# greedy.net
KiCad netlist of a schematic drawn in EAGLE
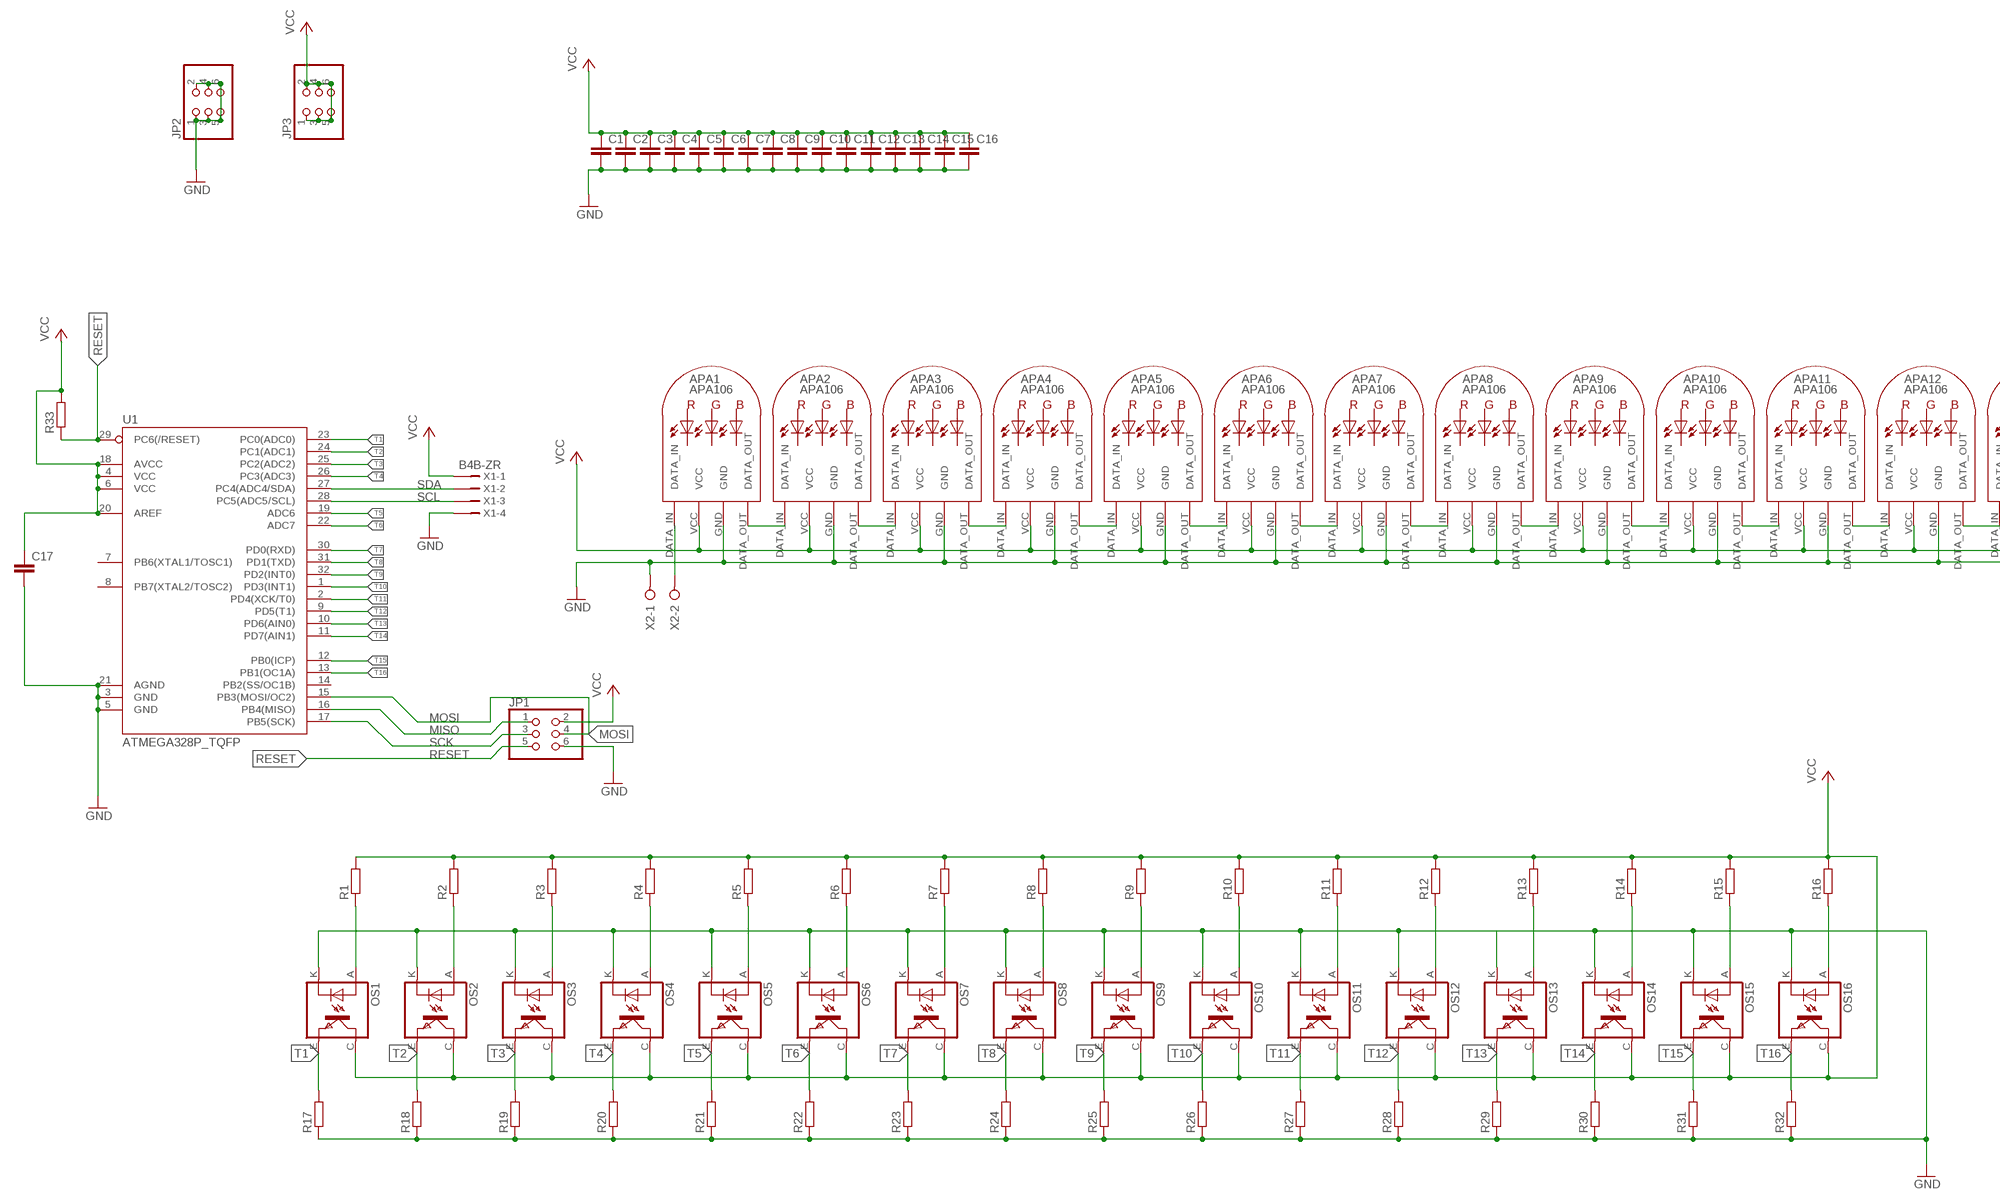
[diagram p0: schematic, sheet 1, part 1 of 2]
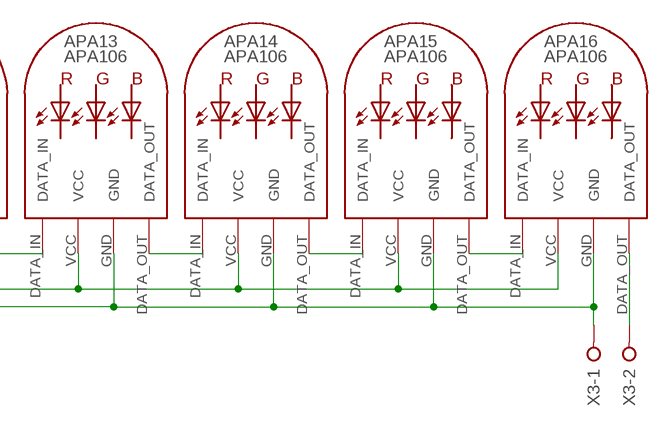
[diagram p1: schematic, sheet 1, part 2 of 2]

(export (version "E")
  (design (tool "Eeschema 10.0.6"))
  (components
    (comp (ref "APA1")
      (value "APA106")
      (footprint "eagle-import:APA_106_8MM")
      (libsource (lib "eagle-import") (part "APA106"))
    )
    (comp (ref "APA2")
      (value "APA106")
      (footprint "eagle-import:APA_106_8MM")
      (libsource (lib "eagle-import") (part "APA106"))
    )
    (comp (ref "APA3")
      (value "APA106")
      (footprint "eagle-import:APA_106_8MM")
      (libsource (lib "eagle-import") (part "APA106"))
    )
    (comp (ref "APA4")
      (value "APA106")
      (footprint "eagle-import:APA_106_8MM")
      (libsource (lib "eagle-import") (part "APA106"))
    )
    (comp (ref "APA5")
      (value "APA106")
      (footprint "eagle-import:APA_106_8MM")
      (libsource (lib "eagle-import") (part "APA106"))
    )
    (comp (ref "APA6")
      (value "APA106")
      (footprint "eagle-import:APA_106_8MM")
      (libsource (lib "eagle-import") (part "APA106"))
    )
    (comp (ref "APA7")
      (value "APA106")
      (footprint "eagle-import:APA_106_8MM")
      (libsource (lib "eagle-import") (part "APA106"))
    )
    (comp (ref "APA8")
      (value "APA106")
      (footprint "eagle-import:APA_106_8MM")
      (libsource (lib "eagle-import") (part "APA106"))
    )
    (comp (ref "APA9")
      (value "APA106")
      (footprint "eagle-import:APA_106_8MM")
      (libsource (lib "eagle-import") (part "APA106"))
    )
    (comp (ref "APA10")
      (value "APA106")
      (footprint "eagle-import:APA_106_8MM")
      (libsource (lib "eagle-import") (part "APA106"))
    )
    (comp (ref "APA11")
      (value "APA106")
      (footprint "eagle-import:APA_106_8MM")
      (libsource (lib "eagle-import") (part "APA106"))
    )
    (comp (ref "APA12")
      (value "APA106")
      (footprint "eagle-import:APA_106_8MM")
      (libsource (lib "eagle-import") (part "APA106"))
    )
    (comp (ref "APA13")
      (value "APA106")
      (footprint "eagle-import:APA_106_8MM")
      (libsource (lib "eagle-import") (part "APA106"))
    )
    (comp (ref "APA14")
      (value "APA106")
      (footprint "eagle-import:APA_106_8MM")
      (libsource (lib "eagle-import") (part "APA106"))
    )
    (comp (ref "APA15")
      (value "APA106")
      (footprint "eagle-import:APA_106_8MM")
      (libsource (lib "eagle-import") (part "APA106"))
    )
    (comp (ref "APA16")
      (value "APA106")
      (footprint "eagle-import:APA_106_8MM")
      (libsource (lib "eagle-import") (part "APA106"))
    )
    (comp (ref "C1")
      (value "C5/3")
      (footprint "eagle-import:C5B3")
      (libsource (lib "eagle-import") (part "C5/3"))
    )
    (comp (ref "C2")
      (value "C5/3")
      (footprint "eagle-import:C5B3")
      (libsource (lib "eagle-import") (part "C5/3"))
    )
    (comp (ref "C3")
      (value "C5/3")
      (footprint "eagle-import:C5B3")
      (libsource (lib "eagle-import") (part "C5/3"))
    )
    (comp (ref "C4")
      (value "C5/3")
      (footprint "eagle-import:C5B3")
      (libsource (lib "eagle-import") (part "C5/3"))
    )
    (comp (ref "C5")
      (value "C5/3")
      (footprint "eagle-import:C5B3")
      (libsource (lib "eagle-import") (part "C5/3"))
    )
    (comp (ref "C6")
      (value "C5/3")
      (footprint "eagle-import:C5B3")
      (libsource (lib "eagle-import") (part "C5/3"))
    )
    (comp (ref "C7")
      (value "C5/3")
      (footprint "eagle-import:C5B3")
      (libsource (lib "eagle-import") (part "C5/3"))
    )
    (comp (ref "C8")
      (value "C5/3")
      (footprint "eagle-import:C5B3")
      (libsource (lib "eagle-import") (part "C5/3"))
    )
    (comp (ref "C9")
      (value "C5/3")
      (footprint "eagle-import:C5B3")
      (libsource (lib "eagle-import") (part "C5/3"))
    )
    (comp (ref "C10")
      (value "C5/3")
      (footprint "eagle-import:C5B3")
      (libsource (lib "eagle-import") (part "C5/3"))
    )
    (comp (ref "C11")
      (value "C5/3")
      (footprint "eagle-import:C5B3")
      (libsource (lib "eagle-import") (part "C5/3"))
    )
    (comp (ref "C12")
      (value "C5/3")
      (footprint "eagle-import:C5B3")
      (libsource (lib "eagle-import") (part "C5/3"))
    )
    (comp (ref "C13")
      (value "C5/3")
      (footprint "eagle-import:C5B3")
      (libsource (lib "eagle-import") (part "C5/3"))
    )
    (comp (ref "C14")
      (value "C5/3")
      (footprint "eagle-import:C5B3")
      (libsource (lib "eagle-import") (part "C5/3"))
    )
    (comp (ref "C15")
      (value "C5/3")
      (footprint "eagle-import:C5B3")
      (libsource (lib "eagle-import") (part "C5/3"))
    )
    (comp (ref "C16")
      (value "C5/3")
      (footprint "eagle-import:C5B3")
      (libsource (lib "eagle-import") (part "C5/3"))
    )
    (comp (ref "C17")
      (value "C-EU025-025X050")
      (footprint "eagle-import:C025-025X050")
      (libsource (lib "eagle-import") (part "C-EU025-025X050"))
    )
    (comp (ref "JP1")
      (value "PINHD-2X3")
      (footprint "eagle-import:2X03")
      (libsource (lib "eagle-import") (part "PINHD-2X3"))
    )
    (comp (ref "JP2")
      (value "PINHD-2X3")
      (footprint "eagle-import:2X03")
      (libsource (lib "eagle-import") (part "PINHD-2X3"))
    )
    (comp (ref "JP3")
      (value "PINHD-2X3")
      (footprint "eagle-import:2X03")
      (libsource (lib "eagle-import") (part "PINHD-2X3"))
    )
    (comp (ref "OS1")
      (value "TCRT5000")
      (footprint "eagle-import:TCRT5000")
      (libsource (lib "eagle-import") (part "TCRT5000"))
    )
    (comp (ref "OS2")
      (value "TCRT5000")
      (footprint "eagle-import:TCRT5000")
      (libsource (lib "eagle-import") (part "TCRT5000"))
    )
    (comp (ref "OS3")
      (value "TCRT5000")
      (footprint "eagle-import:TCRT5000")
      (libsource (lib "eagle-import") (part "TCRT5000"))
    )
    (comp (ref "OS4")
      (value "TCRT5000")
      (footprint "eagle-import:TCRT5000")
      (libsource (lib "eagle-import") (part "TCRT5000"))
    )
    (comp (ref "OS5")
      (value "TCRT5000")
      (footprint "eagle-import:TCRT5000")
      (libsource (lib "eagle-import") (part "TCRT5000"))
    )
    (comp (ref "OS6")
      (value "TCRT5000")
      (footprint "eagle-import:TCRT5000")
      (libsource (lib "eagle-import") (part "TCRT5000"))
    )
    (comp (ref "OS7")
      (value "TCRT5000")
      (footprint "eagle-import:TCRT5000")
      (libsource (lib "eagle-import") (part "TCRT5000"))
    )
    (comp (ref "OS8")
      (value "TCRT5000")
      (footprint "eagle-import:TCRT5000")
      (libsource (lib "eagle-import") (part "TCRT5000"))
    )
    (comp (ref "OS9")
      (value "TCRT5000")
      (footprint "eagle-import:TCRT5000")
      (libsource (lib "eagle-import") (part "TCRT5000"))
    )
    (comp (ref "OS10")
      (value "TCRT5000")
      (footprint "eagle-import:TCRT5000")
      (libsource (lib "eagle-import") (part "TCRT5000"))
    )
    (comp (ref "OS11")
      (value "TCRT5000")
      (footprint "eagle-import:TCRT5000")
      (libsource (lib "eagle-import") (part "TCRT5000"))
    )
    (comp (ref "OS12")
      (value "TCRT5000")
      (footprint "eagle-import:TCRT5000")
      (libsource (lib "eagle-import") (part "TCRT5000"))
    )
    (comp (ref "OS13")
      (value "TCRT5000")
      (footprint "eagle-import:TCRT5000")
      (libsource (lib "eagle-import") (part "TCRT5000"))
    )
    (comp (ref "OS14")
      (value "TCRT5000")
      (footprint "eagle-import:TCRT5000")
      (libsource (lib "eagle-import") (part "TCRT5000"))
    )
    (comp (ref "OS15")
      (value "TCRT5000")
      (footprint "eagle-import:TCRT5000")
      (libsource (lib "eagle-import") (part "TCRT5000"))
    )
    (comp (ref "OS16")
      (value "TCRT5000")
      (footprint "eagle-import:TCRT5000")
      (libsource (lib "eagle-import") (part "TCRT5000"))
    )
    (comp (ref "R1")
      (value "R-EU_R0805")
      (footprint "eagle-import:R0805")
      (libsource (lib "eagle-import") (part "R-EU_R0805"))
    )
    (comp (ref "R2")
      (value "R-EU_R0805")
      (footprint "eagle-import:R0805")
      (libsource (lib "eagle-import") (part "R-EU_R0805"))
    )
    (comp (ref "R3")
      (value "R-EU_R0805")
      (footprint "eagle-import:R0805")
      (libsource (lib "eagle-import") (part "R-EU_R0805"))
    )
    (comp (ref "R4")
      (value "R-EU_R0805")
      (footprint "eagle-import:R0805")
      (libsource (lib "eagle-import") (part "R-EU_R0805"))
    )
    (comp (ref "R5")
      (value "R-EU_R0805")
      (footprint "eagle-import:R0805")
      (libsource (lib "eagle-import") (part "R-EU_R0805"))
    )
    (comp (ref "R6")
      (value "R-EU_R0805")
      (footprint "eagle-import:R0805")
      (libsource (lib "eagle-import") (part "R-EU_R0805"))
    )
    (comp (ref "R7")
      (value "R-EU_R0805")
      (footprint "eagle-import:R0805")
      (libsource (lib "eagle-import") (part "R-EU_R0805"))
    )
    (comp (ref "R8")
      (value "R-EU_R0805")
      (footprint "eagle-import:R0805")
      (libsource (lib "eagle-import") (part "R-EU_R0805"))
    )
    (comp (ref "R9")
      (value "R-EU_R0805")
      (footprint "eagle-import:R0805")
      (libsource (lib "eagle-import") (part "R-EU_R0805"))
    )
    (comp (ref "R10")
      (value "R-EU_R0805")
      (footprint "eagle-import:R0805")
      (libsource (lib "eagle-import") (part "R-EU_R0805"))
    )
    (comp (ref "R11")
      (value "R-EU_R0805")
      (footprint "eagle-import:R0805")
      (libsource (lib "eagle-import") (part "R-EU_R0805"))
    )
    (comp (ref "R12")
      (value "R-EU_R0805")
      (footprint "eagle-import:R0805")
      (libsource (lib "eagle-import") (part "R-EU_R0805"))
    )
    (comp (ref "R13")
      (value "R-EU_R0805")
      (footprint "eagle-import:R0805")
      (libsource (lib "eagle-import") (part "R-EU_R0805"))
    )
    (comp (ref "R14")
      (value "R-EU_R0805")
      (footprint "eagle-import:R0805")
      (libsource (lib "eagle-import") (part "R-EU_R0805"))
    )
    (comp (ref "R15")
      (value "R-EU_R0805")
      (footprint "eagle-import:R0805")
      (libsource (lib "eagle-import") (part "R-EU_R0805"))
    )
    (comp (ref "R16")
      (value "R-EU_R0805")
      (footprint "eagle-import:R0805")
      (libsource (lib "eagle-import") (part "R-EU_R0805"))
    )
    (comp (ref "R17")
      (value "R-EU_R0805")
      (footprint "eagle-import:R0805")
      (libsource (lib "eagle-import") (part "R-EU_R0805"))
    )
    (comp (ref "R18")
      (value "R-EU_R0805")
      (footprint "eagle-import:R0805")
      (libsource (lib "eagle-import") (part "R-EU_R0805"))
    )
    (comp (ref "R19")
      (value "R-EU_R0805")
      (footprint "eagle-import:R0805")
      (libsource (lib "eagle-import") (part "R-EU_R0805"))
    )
    (comp (ref "R20")
      (value "R-EU_R0805")
      (footprint "eagle-import:R0805")
      (libsource (lib "eagle-import") (part "R-EU_R0805"))
    )
    (comp (ref "R21")
      (value "R-EU_R0805")
      (footprint "eagle-import:R0805")
      (libsource (lib "eagle-import") (part "R-EU_R0805"))
    )
    (comp (ref "R22")
      (value "R-EU_R0805")
      (footprint "eagle-import:R0805")
      (libsource (lib "eagle-import") (part "R-EU_R0805"))
    )
    (comp (ref "R23")
      (value "R-EU_R0805")
      (footprint "eagle-import:R0805")
      (libsource (lib "eagle-import") (part "R-EU_R0805"))
    )
    (comp (ref "R24")
      (value "R-EU_R0805")
      (footprint "eagle-import:R0805")
      (libsource (lib "eagle-import") (part "R-EU_R0805"))
    )
    (comp (ref "R25")
      (value "R-EU_R0805")
      (footprint "eagle-import:R0805")
      (libsource (lib "eagle-import") (part "R-EU_R0805"))
    )
    (comp (ref "R26")
      (value "R-EU_R0805")
      (footprint "eagle-import:R0805")
      (libsource (lib "eagle-import") (part "R-EU_R0805"))
    )
    (comp (ref "R27")
      (value "R-EU_R0805")
      (footprint "eagle-import:R0805")
      (libsource (lib "eagle-import") (part "R-EU_R0805"))
    )
    (comp (ref "R28")
      (value "R-EU_R0805")
      (footprint "eagle-import:R0805")
      (libsource (lib "eagle-import") (part "R-EU_R0805"))
    )
    (comp (ref "R29")
      (value "R-EU_R0805")
      (footprint "eagle-import:R0805")
      (libsource (lib "eagle-import") (part "R-EU_R0805"))
    )
    (comp (ref "R30")
      (value "R-EU_R0805")
      (footprint "eagle-import:R0805")
      (libsource (lib "eagle-import") (part "R-EU_R0805"))
    )
    (comp (ref "R31")
      (value "R-EU_R0805")
      (footprint "eagle-import:R0805")
      (libsource (lib "eagle-import") (part "R-EU_R0805"))
    )
    (comp (ref "R32")
      (value "R-EU_R0805")
      (footprint "eagle-import:R0805")
      (libsource (lib "eagle-import") (part "R-EU_R0805"))
    )
    (comp (ref "R33")
      (value "R-EU_R0805")
      (footprint "eagle-import:R0805")
      (libsource (lib "eagle-import") (part "R-EU_R0805"))
    )
    (comp (ref "U1")
      (value "ATMEGA328P_TQFP")
      (footprint "eagle-import:TQFP32-08")
      (libsource (lib "eagle-import") (part "ATMEGA328P_TQFP"))
    )
    (comp (ref "X1")
      (value "B4B-ZR")
      (footprint "eagle-import:B4B-ZR")
      (fields (field (name "MF") "FARNELL") (field (name "MPN") "B4B-ZR(LF)(SN)"))
      (libsource (lib "eagle-import") (part "?4B-ZRB"))
    )
    (comp (ref "X2")
      (value "W237-02P")
      (footprint "eagle-import:W237-132")
      (libsource (lib "eagle-import") (part "W237-02P"))
    )
    (comp (ref "X3")
      (value "W237-02P")
      (footprint "eagle-import:W237-132")
      (libsource (lib "eagle-import") (part "W237-02P"))
    )
  )
  (nets
    (net (code "1") (name "/MISO") (class "Default")
      (node (ref "JP1") (pin "1") (pinfunction "1_1") (pintype "passive"))
      (node (ref "U1") (pin "16") (pinfunction "PB4(MISO)_16") (pintype "bidirectional"))
    )
    (net (code "2") (name "/SCK") (class "Default")
      (node (ref "JP1") (pin "3") (pinfunction "3_3") (pintype "passive"))
      (node (ref "U1") (pin "17") (pinfunction "PB5(SCK)_17") (pintype "bidirectional"))
    )
    (net (code "3") (name "/SCL") (class "Default")
      (node (ref "U1") (pin "28") (pinfunction "PC5(ADC5/SCL)_28") (pintype "bidirectional"))
      (node (ref "X1") (pin "3") (pinfunction "1_3") (pintype "passive"))
    )
    (net (code "4") (name "/SDA") (class "Default")
      (node (ref "U1") (pin "27") (pinfunction "PC4(ADC4/SDA)_27") (pintype "bidirectional"))
      (node (ref "X1") (pin "2") (pinfunction "1_2") (pintype "passive"))
    )
    (net (code "5") (name "GND") (class "Default")
      (node (ref "APA1") (pin "GND") (pinfunction "GND_GND") (pintype "power_in"))
      (node (ref "APA10") (pin "GND") (pinfunction "GND_GND") (pintype "power_in"))
      (node (ref "APA11") (pin "GND") (pinfunction "GND_GND") (pintype "power_in"))
      (node (ref "APA12") (pin "GND") (pinfunction "GND_GND") (pintype "power_in"))
      (node (ref "APA13") (pin "GND") (pinfunction "GND_GND") (pintype "power_in"))
      (node (ref "APA14") (pin "GND") (pinfunction "GND_GND") (pintype "power_in"))
      (node (ref "APA15") (pin "GND") (pinfunction "GND_GND") (pintype "power_in"))
      (node (ref "APA16") (pin "GND") (pinfunction "GND_GND") (pintype "power_in"))
      (node (ref "APA2") (pin "GND") (pinfunction "GND_GND") (pintype "power_in"))
      (node (ref "APA3") (pin "GND") (pinfunction "GND_GND") (pintype "power_in"))
      (node (ref "APA4") (pin "GND") (pinfunction "GND_GND") (pintype "power_in"))
      (node (ref "APA5") (pin "GND") (pinfunction "GND_GND") (pintype "power_in"))
      (node (ref "APA6") (pin "GND") (pinfunction "GND_GND") (pintype "power_in"))
      (node (ref "APA7") (pin "GND") (pinfunction "GND_GND") (pintype "power_in"))
      (node (ref "APA8") (pin "GND") (pinfunction "GND_GND") (pintype "power_in"))
      (node (ref "APA9") (pin "GND") (pinfunction "GND_GND") (pintype "power_in"))
      (node (ref "C1") (pin "2") (pinfunction "2_2") (pintype "passive"))
      (node (ref "C10") (pin "2") (pinfunction "2_2") (pintype "passive"))
      (node (ref "C11") (pin "2") (pinfunction "2_2") (pintype "passive"))
      (node (ref "C12") (pin "2") (pinfunction "2_2") (pintype "passive"))
      (node (ref "C13") (pin "2") (pinfunction "2_2") (pintype "passive"))
      (node (ref "C14") (pin "2") (pinfunction "2_2") (pintype "passive"))
      (node (ref "C15") (pin "2") (pinfunction "2_2") (pintype "passive"))
      (node (ref "C16") (pin "2") (pinfunction "2_2") (pintype "passive"))
      (node (ref "C17") (pin "2") (pinfunction "2_2") (pintype "passive"))
      (node (ref "C2") (pin "2") (pinfunction "2_2") (pintype "passive"))
      (node (ref "C3") (pin "2") (pinfunction "2_2") (pintype "passive"))
      (node (ref "C4") (pin "2") (pinfunction "2_2") (pintype "passive"))
      (node (ref "C5") (pin "2") (pinfunction "2_2") (pintype "passive"))
      (node (ref "C6") (pin "2") (pinfunction "2_2") (pintype "passive"))
      (node (ref "C7") (pin "2") (pinfunction "2_2") (pintype "passive"))
      (node (ref "C8") (pin "2") (pinfunction "2_2") (pintype "passive"))
      (node (ref "C9") (pin "2") (pinfunction "2_2") (pintype "passive"))
      (node (ref "JP1") (pin "6") (pinfunction "6_6") (pintype "passive"))
      (node (ref "JP2") (pin "1") (pinfunction "1_1") (pintype "passive"))
      (node (ref "JP2") (pin "2") (pinfunction "2_2") (pintype "passive"))
      (node (ref "JP2") (pin "3") (pinfunction "3_3") (pintype "passive"))
      (node (ref "JP2") (pin "4") (pinfunction "4_4") (pintype "passive"))
      (node (ref "JP2") (pin "5") (pinfunction "5_5") (pintype "passive"))
      (node (ref "JP2") (pin "6") (pinfunction "6_6") (pintype "passive"))
      (node (ref "OS1") (pin "K") (pinfunction "CATHODE_K") (pintype "passive"))
      (node (ref "OS10") (pin "K") (pinfunction "CATHODE_K") (pintype "passive"))
      (node (ref "OS11") (pin "K") (pinfunction "CATHODE_K") (pintype "passive"))
      (node (ref "OS12") (pin "K") (pinfunction "CATHODE_K") (pintype "passive"))
      (node (ref "OS13") (pin "K") (pinfunction "CATHODE_K") (pintype "passive"))
      (node (ref "OS14") (pin "K") (pinfunction "CATHODE_K") (pintype "passive"))
      (node (ref "OS15") (pin "K") (pinfunction "CATHODE_K") (pintype "passive"))
      (node (ref "OS16") (pin "K") (pinfunction "CATHODE_K") (pintype "passive"))
      (node (ref "OS2") (pin "K") (pinfunction "CATHODE_K") (pintype "passive"))
      (node (ref "OS3") (pin "K") (pinfunction "CATHODE_K") (pintype "passive"))
      (node (ref "OS4") (pin "K") (pinfunction "CATHODE_K") (pintype "passive"))
      (node (ref "OS5") (pin "K") (pinfunction "CATHODE_K") (pintype "passive"))
      (node (ref "OS6") (pin "K") (pinfunction "CATHODE_K") (pintype "passive"))
      (node (ref "OS7") (pin "K") (pinfunction "CATHODE_K") (pintype "passive"))
      (node (ref "OS8") (pin "K") (pinfunction "CATHODE_K") (pintype "passive"))
      (node (ref "OS9") (pin "K") (pinfunction "CATHODE_K") (pintype "passive"))
      (node (ref "R17") (pin "1") (pinfunction "1_1") (pintype "passive"))
      (node (ref "R17") (pin "11") (pinfunction "1_11") (pintype "passive"))
      (node (ref "R18") (pin "1") (pinfunction "1_1") (pintype "passive"))
      (node (ref "R18") (pin "11") (pinfunction "1_11") (pintype "passive"))
      (node (ref "R19") (pin "1") (pinfunction "1_1") (pintype "passive"))
      (node (ref "R19") (pin "11") (pinfunction "1_11") (pintype "passive"))
      (node (ref "R20") (pin "1") (pinfunction "1_1") (pintype "passive"))
      (node (ref "R20") (pin "11") (pinfunction "1_11") (pintype "passive"))
      (node (ref "R21") (pin "1") (pinfunction "1_1") (pintype "passive"))
      (node (ref "R21") (pin "11") (pinfunction "1_11") (pintype "passive"))
      (node (ref "R22") (pin "1") (pinfunction "1_1") (pintype "passive"))
      (node (ref "R22") (pin "11") (pinfunction "1_11") (pintype "passive"))
      (node (ref "R23") (pin "1") (pinfunction "1_1") (pintype "passive"))
      (node (ref "R23") (pin "11") (pinfunction "1_11") (pintype "passive"))
      (node (ref "R24") (pin "1") (pinfunction "1_1") (pintype "passive"))
      (node (ref "R24") (pin "11") (pinfunction "1_11") (pintype "passive"))
      (node (ref "R25") (pin "1") (pinfunction "1_1") (pintype "passive"))
      (node (ref "R25") (pin "11") (pinfunction "1_11") (pintype "passive"))
      (node (ref "R26") (pin "1") (pinfunction "1_1") (pintype "passive"))
      (node (ref "R26") (pin "11") (pinfunction "1_11") (pintype "passive"))
      (node (ref "R27") (pin "1") (pinfunction "1_1") (pintype "passive"))
      (node (ref "R27") (pin "11") (pinfunction "1_11") (pintype "passive"))
      (node (ref "R28") (pin "1") (pinfunction "1_1") (pintype "passive"))
      (node (ref "R28") (pin "11") (pinfunction "1_11") (pintype "passive"))
      (node (ref "R29") (pin "1") (pinfunction "1_1") (pintype "passive"))
      (node (ref "R29") (pin "11") (pinfunction "1_11") (pintype "passive"))
      (node (ref "R30") (pin "1") (pinfunction "1_1") (pintype "passive"))
      (node (ref "R30") (pin "11") (pinfunction "1_11") (pintype "passive"))
      (node (ref "R31") (pin "1") (pinfunction "1_1") (pintype "passive"))
      (node (ref "R31") (pin "11") (pinfunction "1_11") (pintype "passive"))
      (node (ref "R32") (pin "1") (pinfunction "1_1") (pintype "passive"))
      (node (ref "R32") (pin "11") (pinfunction "1_11") (pintype "passive"))
      (node (ref "U1") (pin "21") (pinfunction "AGND_21") (pintype "bidirectional"))
      (node (ref "U1") (pin "3") (pinfunction "GND_3") (pintype "bidirectional"))
      (node (ref "U1") (pin "5") (pinfunction "GND_5") (pintype "bidirectional"))
      (node (ref "X1") (pin "4") (pinfunction "1_4") (pintype "passive"))
      (node (ref "X2") (pin "1") (pinfunction "KL_1") (pintype "passive"))
      (node (ref "X3") (pin "1") (pinfunction "KL_1") (pintype "passive"))
    )
    (net (code "6") (name "MOSI") (class "Default")
      (node (ref "JP1") (pin "4") (pinfunction "4_4") (pintype "passive"))
      (node (ref "U1") (pin "15") (pinfunction "PB3(MOSI/OC2)_15") (pintype "bidirectional"))
    )
    (net (code "7") (name "Net-(APA1-PadDATA_OUT)") (class "Default")
      (node (ref "APA1") (pin "DATA_OUT") (pinfunction "DATA_OUT_DATA_OUT") (pintype "bidirectional"))
      (node (ref "APA2") (pin "DATA_IN") (pinfunction "DATA_IN_DATA_IN") (pintype "bidirectional"))
    )
    (net (code "8") (name "Net-(APA2-PadDATA_OUT)") (class "Default")
      (node (ref "APA2") (pin "DATA_OUT") (pinfunction "DATA_OUT_DATA_OUT") (pintype "bidirectional"))
      (node (ref "APA3") (pin "DATA_IN") (pinfunction "DATA_IN_DATA_IN") (pintype "bidirectional"))
    )
    (net (code "9") (name "Net-(APA3-PadDATA_OUT)") (class "Default")
      (node (ref "APA3") (pin "DATA_OUT") (pinfunction "DATA_OUT_DATA_OUT") (pintype "bidirectional"))
      (node (ref "APA4") (pin "DATA_IN") (pinfunction "DATA_IN_DATA_IN") (pintype "bidirectional"))
    )
    (net (code "10") (name "Net-(APA4-PadDATA_OUT)") (class "Default")
      (node (ref "APA4") (pin "DATA_OUT") (pinfunction "DATA_OUT_DATA_OUT") (pintype "bidirectional"))
      (node (ref "APA5") (pin "DATA_IN") (pinfunction "DATA_IN_DATA_IN") (pintype "bidirectional"))
    )
    (net (code "11") (name "Net-(APA5-PadDATA_OUT)") (class "Default")
      (node (ref "APA5") (pin "DATA_OUT") (pinfunction "DATA_OUT_DATA_OUT") (pintype "bidirectional"))
      (node (ref "APA6") (pin "DATA_IN") (pinfunction "DATA_IN_DATA_IN") (pintype "bidirectional"))
    )
    (net (code "12") (name "Net-(APA6-PadDATA_OUT)") (class "Default")
      (node (ref "APA6") (pin "DATA_OUT") (pinfunction "DATA_OUT_DATA_OUT") (pintype "bidirectional"))
      (node (ref "APA7") (pin "DATA_IN") (pinfunction "DATA_IN_DATA_IN") (pintype "bidirectional"))
    )
    (net (code "13") (name "Net-(APA7-PadDATA_OUT)") (class "Default")
      (node (ref "APA7") (pin "DATA_OUT") (pinfunction "DATA_OUT_DATA_OUT") (pintype "bidirectional"))
      (node (ref "APA8") (pin "DATA_IN") (pinfunction "DATA_IN_DATA_IN") (pintype "bidirectional"))
    )
    (net (code "14") (name "Net-(APA8-PadDATA_OUT)") (class "Default")
      (node (ref "APA8") (pin "DATA_OUT") (pinfunction "DATA_OUT_DATA_OUT") (pintype "bidirectional"))
      (node (ref "APA9") (pin "DATA_IN") (pinfunction "DATA_IN_DATA_IN") (pintype "bidirectional"))
    )
    (net (code "15") (name "Net-(APA10-PadDATA_IN)") (class "Default")
      (node (ref "APA10") (pin "DATA_IN") (pinfunction "DATA_IN_DATA_IN") (pintype "bidirectional"))
      (node (ref "APA9") (pin "DATA_OUT") (pinfunction "DATA_OUT_DATA_OUT") (pintype "bidirectional"))
    )
    (net (code "16") (name "Net-(APA10-PadDATA_OUT)") (class "Default")
      (node (ref "APA10") (pin "DATA_OUT") (pinfunction "DATA_OUT_DATA_OUT") (pintype "bidirectional"))
      (node (ref "APA11") (pin "DATA_IN") (pinfunction "DATA_IN_DATA_IN") (pintype "bidirectional"))
    )
    (net (code "17") (name "Net-(APA11-PadDATA_OUT)") (class "Default")
      (node (ref "APA11") (pin "DATA_OUT") (pinfunction "DATA_OUT_DATA_OUT") (pintype "bidirectional"))
      (node (ref "APA12") (pin "DATA_IN") (pinfunction "DATA_IN_DATA_IN") (pintype "bidirectional"))
    )
    (net (code "18") (name "Net-(APA12-PadDATA_OUT)") (class "Default")
      (node (ref "APA12") (pin "DATA_OUT") (pinfunction "DATA_OUT_DATA_OUT") (pintype "bidirectional"))
      (node (ref "APA13") (pin "DATA_IN") (pinfunction "DATA_IN_DATA_IN") (pintype "bidirectional"))
    )
    (net (code "19") (name "Net-(APA13-PadDATA_OUT)") (class "Default")
      (node (ref "APA13") (pin "DATA_OUT") (pinfunction "DATA_OUT_DATA_OUT") (pintype "bidirectional"))
      (node (ref "APA14") (pin "DATA_IN") (pinfunction "DATA_IN_DATA_IN") (pintype "bidirectional"))
    )
    (net (code "20") (name "Net-(APA14-PadDATA_OUT)") (class "Default")
      (node (ref "APA14") (pin "DATA_OUT") (pinfunction "DATA_OUT_DATA_OUT") (pintype "bidirectional"))
      (node (ref "APA15") (pin "DATA_IN") (pinfunction "DATA_IN_DATA_IN") (pintype "bidirectional"))
    )
    (net (code "21") (name "Net-(APA15-PadDATA_OUT)") (class "Default")
      (node (ref "APA15") (pin "DATA_OUT") (pinfunction "DATA_OUT_DATA_OUT") (pintype "bidirectional"))
      (node (ref "APA16") (pin "DATA_IN") (pinfunction "DATA_IN_DATA_IN") (pintype "bidirectional"))
    )
    (net (code "22") (name "Net-(OS1-ANODE)") (class "Default")
      (node (ref "OS1") (pin "A") (pinfunction "ANODE_A") (pintype "passive"))
      (node (ref "R1") (pin "1") (pinfunction "1_1") (pintype "passive"))
      (node (ref "R1") (pin "11") (pinfunction "1_11") (pintype "passive"))
    )
    (net (code "23") (name "Net-(OS2-ANODE)") (class "Default")
      (node (ref "OS2") (pin "A") (pinfunction "ANODE_A") (pintype "passive"))
      (node (ref "R2") (pin "1") (pinfunction "1_1") (pintype "passive"))
      (node (ref "R2") (pin "11") (pinfunction "1_11") (pintype "passive"))
    )
    (net (code "24") (name "Net-(OS3-ANODE)") (class "Default")
      (node (ref "OS3") (pin "A") (pinfunction "ANODE_A") (pintype "passive"))
      (node (ref "R3") (pin "1") (pinfunction "1_1") (pintype "passive"))
      (node (ref "R3") (pin "11") (pinfunction "1_11") (pintype "passive"))
    )
    (net (code "25") (name "Net-(OS4-ANODE)") (class "Default")
      (node (ref "OS4") (pin "A") (pinfunction "ANODE_A") (pintype "passive"))
      (node (ref "R4") (pin "1") (pinfunction "1_1") (pintype "passive"))
      (node (ref "R4") (pin "11") (pinfunction "1_11") (pintype "passive"))
    )
    (net (code "26") (name "Net-(OS5-ANODE)") (class "Default")
      (node (ref "OS5") (pin "A") (pinfunction "ANODE_A") (pintype "passive"))
      (node (ref "R5") (pin "1") (pinfunction "1_1") (pintype "passive"))
      (node (ref "R5") (pin "11") (pinfunction "1_11") (pintype "passive"))
    )
    (net (code "27") (name "Net-(OS6-ANODE)") (class "Default")
      (node (ref "OS6") (pin "A") (pinfunction "ANODE_A") (pintype "passive"))
      (node (ref "R6") (pin "1") (pinfunction "1_1") (pintype "passive"))
      (node (ref "R6") (pin "11") (pinfunction "1_11") (pintype "passive"))
    )
    (net (code "28") (name "Net-(OS7-ANODE)") (class "Default")
      (node (ref "OS7") (pin "A") (pinfunction "ANODE_A") (pintype "passive"))
      (node (ref "R7") (pin "1") (pinfunction "1_1") (pintype "passive"))
      (node (ref "R7") (pin "11") (pinfunction "1_11") (pintype "passive"))
    )
    (net (code "29") (name "Net-(OS8-ANODE)") (class "Default")
      (node (ref "OS8") (pin "A") (pinfunction "ANODE_A") (pintype "passive"))
      (node (ref "R8") (pin "1") (pinfunction "1_1") (pintype "passive"))
      (node (ref "R8") (pin "11") (pinfunction "1_11") (pintype "passive"))
    )
    (net (code "30") (name "Net-(OS9-ANODE)") (class "Default")
      (node (ref "OS9") (pin "A") (pinfunction "ANODE_A") (pintype "passive"))
      (node (ref "R9") (pin "1") (pinfunction "1_1") (pintype "passive"))
      (node (ref "R9") (pin "11") (pinfunction "1_11") (pintype "passive"))
    )
    (net (code "31") (name "Net-(OS10-ANODE)") (class "Default")
      (node (ref "OS10") (pin "A") (pinfunction "ANODE_A") (pintype "passive"))
      (node (ref "R10") (pin "1") (pinfunction "1_1") (pintype "passive"))
      (node (ref "R10") (pin "11") (pinfunction "1_11") (pintype "passive"))
    )
    (net (code "32") (name "Net-(OS11-ANODE)") (class "Default")
      (node (ref "OS11") (pin "A") (pinfunction "ANODE_A") (pintype "passive"))
      (node (ref "R11") (pin "1") (pinfunction "1_1") (pintype "passive"))
      (node (ref "R11") (pin "11") (pinfunction "1_11") (pintype "passive"))
    )
    (net (code "33") (name "Net-(OS12-ANODE)") (class "Default")
      (node (ref "OS12") (pin "A") (pinfunction "ANODE_A") (pintype "passive"))
      (node (ref "R12") (pin "1") (pinfunction "1_1") (pintype "passive"))
      (node (ref "R12") (pin "11") (pinfunction "1_11") (pintype "passive"))
    )
    (net (code "34") (name "Net-(OS13-ANODE)") (class "Default")
      (node (ref "OS13") (pin "A") (pinfunction "ANODE_A") (pintype "passive"))
      (node (ref "R13") (pin "1") (pinfunction "1_1") (pintype "passive"))
      (node (ref "R13") (pin "11") (pinfunction "1_11") (pintype "passive"))
    )
    (net (code "35") (name "Net-(OS14-ANODE)") (class "Default")
      (node (ref "OS14") (pin "A") (pinfunction "ANODE_A") (pintype "passive"))
      (node (ref "R14") (pin "1") (pinfunction "1_1") (pintype "passive"))
      (node (ref "R14") (pin "11") (pinfunction "1_11") (pintype "passive"))
    )
    (net (code "36") (name "Net-(OS15-ANODE)") (class "Default")
      (node (ref "OS15") (pin "A") (pinfunction "ANODE_A") (pintype "passive"))
      (node (ref "R15") (pin "1") (pinfunction "1_1") (pintype "passive"))
      (node (ref "R15") (pin "11") (pinfunction "1_11") (pintype "passive"))
    )
    (net (code "37") (name "Net-(OS16-ANODE)") (class "Default")
      (node (ref "OS16") (pin "A") (pinfunction "ANODE_A") (pintype "passive"))
      (node (ref "R16") (pin "1") (pinfunction "1_1") (pintype "passive"))
      (node (ref "R16") (pin "11") (pinfunction "1_11") (pintype "passive"))
    )
    (net (code "38") (name "Net-(X2B-KL)") (class "Default")
      (node (ref "APA1") (pin "DATA_IN") (pinfunction "DATA_IN_DATA_IN") (pintype "bidirectional"))
      (node (ref "X2") (pin "2") (pinfunction "KL_2") (pintype "passive"))
    )
    (net (code "39") (name "Net-(X3B-KL)") (class "Default")
      (node (ref "APA16") (pin "DATA_OUT") (pinfunction "DATA_OUT_DATA_OUT") (pintype "bidirectional"))
      (node (ref "X3") (pin "2") (pinfunction "KL_2") (pintype "passive"))
    )
    (net (code "40") (name "RESET") (class "Default")
      (node (ref "JP1") (pin "5") (pinfunction "5_5") (pintype "passive"))
      (node (ref "R33") (pin "1") (pinfunction "1_1") (pintype "passive"))
      (node (ref "R33") (pin "11") (pinfunction "1_11") (pintype "passive"))
      (node (ref "U1") (pin "29") (pinfunction "PC6(/RESET)_29") (pintype "bidirectional"))
    )
    (net (code "41") (name "T1") (class "Default")
      (node (ref "OS1") (pin "E") (pinfunction "EMITTER_E") (pintype "passive"))
      (node (ref "R17") (pin "2") (pinfunction "2_2") (pintype "passive"))
      (node (ref "R17") (pin "21") (pinfunction "2_21") (pintype "passive"))
      (node (ref "U1") (pin "23") (pinfunction "PC0(ADC0)_23") (pintype "bidirectional"))
    )
    (net (code "42") (name "T2") (class "Default")
      (node (ref "OS2") (pin "E") (pinfunction "EMITTER_E") (pintype "passive"))
      (node (ref "R18") (pin "2") (pinfunction "2_2") (pintype "passive"))
      (node (ref "R18") (pin "21") (pinfunction "2_21") (pintype "passive"))
      (node (ref "U1") (pin "24") (pinfunction "PC1(ADC1)_24") (pintype "bidirectional"))
    )
    (net (code "43") (name "T3") (class "Default")
      (node (ref "OS3") (pin "E") (pinfunction "EMITTER_E") (pintype "passive"))
      (node (ref "R19") (pin "2") (pinfunction "2_2") (pintype "passive"))
      (node (ref "R19") (pin "21") (pinfunction "2_21") (pintype "passive"))
      (node (ref "U1") (pin "25") (pinfunction "PC2(ADC2)_25") (pintype "bidirectional"))
    )
    (net (code "44") (name "T4") (class "Default")
      (node (ref "OS4") (pin "E") (pinfunction "EMITTER_E") (pintype "passive"))
      (node (ref "R20") (pin "2") (pinfunction "2_2") (pintype "passive"))
      (node (ref "R20") (pin "21") (pinfunction "2_21") (pintype "passive"))
      (node (ref "U1") (pin "26") (pinfunction "PC3(ADC3)_26") (pintype "bidirectional"))
    )
    (net (code "45") (name "T5") (class "Default")
      (node (ref "OS5") (pin "E") (pinfunction "EMITTER_E") (pintype "passive"))
      (node (ref "R21") (pin "2") (pinfunction "2_2") (pintype "passive"))
      (node (ref "R21") (pin "21") (pinfunction "2_21") (pintype "passive"))
      (node (ref "U1") (pin "19") (pinfunction "ADC6_19") (pintype "bidirectional"))
    )
    (net (code "46") (name "T6") (class "Default")
      (node (ref "OS6") (pin "E") (pinfunction "EMITTER_E") (pintype "passive"))
      (node (ref "R22") (pin "2") (pinfunction "2_2") (pintype "passive"))
      (node (ref "R22") (pin "21") (pinfunction "2_21") (pintype "passive"))
      (node (ref "U1") (pin "22") (pinfunction "ADC7_22") (pintype "bidirectional"))
    )
    (net (code "47") (name "T7") (class "Default")
      (node (ref "OS7") (pin "E") (pinfunction "EMITTER_E") (pintype "passive"))
      (node (ref "R23") (pin "2") (pinfunction "2_2") (pintype "passive"))
      (node (ref "R23") (pin "21") (pinfunction "2_21") (pintype "passive"))
      (node (ref "U1") (pin "30") (pinfunction "PD0(RXD)_30") (pintype "bidirectional"))
    )
    (net (code "48") (name "T8") (class "Default")
      (node (ref "OS8") (pin "E") (pinfunction "EMITTER_E") (pintype "passive"))
      (node (ref "R24") (pin "2") (pinfunction "2_2") (pintype "passive"))
      (node (ref "R24") (pin "21") (pinfunction "2_21") (pintype "passive"))
      (node (ref "U1") (pin "31") (pinfunction "PD1(TXD)_31") (pintype "bidirectional"))
    )
    (net (code "49") (name "T9") (class "Default")
      (node (ref "OS9") (pin "E") (pinfunction "EMITTER_E") (pintype "passive"))
      (node (ref "R25") (pin "2") (pinfunction "2_2") (pintype "passive"))
      (node (ref "R25") (pin "21") (pinfunction "2_21") (pintype "passive"))
      (node (ref "U1") (pin "32") (pinfunction "PD2(INT0)_32") (pintype "bidirectional"))
    )
    (net (code "50") (name "T10") (class "Default")
      (node (ref "OS10") (pin "E") (pinfunction "EMITTER_E") (pintype "passive"))
      (node (ref "R26") (pin "2") (pinfunction "2_2") (pintype "passive"))
      (node (ref "R26") (pin "21") (pinfunction "2_21") (pintype "passive"))
      (node (ref "U1") (pin "1") (pinfunction "PD3(INT1)_1") (pintype "bidirectional"))
    )
    (net (code "51") (name "T11") (class "Default")
      (node (ref "OS11") (pin "E") (pinfunction "EMITTER_E") (pintype "passive"))
      (node (ref "R27") (pin "2") (pinfunction "2_2") (pintype "passive"))
      (node (ref "R27") (pin "21") (pinfunction "2_21") (pintype "passive"))
      (node (ref "U1") (pin "2") (pinfunction "PD4(XCK/T0)_2") (pintype "bidirectional"))
    )
    (net (code "52") (name "T12") (class "Default")
      (node (ref "OS12") (pin "E") (pinfunction "EMITTER_E") (pintype "passive"))
      (node (ref "R28") (pin "2") (pinfunction "2_2") (pintype "passive"))
      (node (ref "R28") (pin "21") (pinfunction "2_21") (pintype "passive"))
      (node (ref "U1") (pin "9") (pinfunction "PD5(T1)_9") (pintype "bidirectional"))
    )
    (net (code "53") (name "T13") (class "Default")
      (node (ref "OS13") (pin "E") (pinfunction "EMITTER_E") (pintype "passive"))
      (node (ref "R29") (pin "2") (pinfunction "2_2") (pintype "passive"))
      (node (ref "R29") (pin "21") (pinfunction "2_21") (pintype "passive"))
      (node (ref "U1") (pin "10") (pinfunction "PD6(AIN0)_10") (pintype "bidirectional"))
    )
    (net (code "54") (name "T14") (class "Default")
      (node (ref "OS14") (pin "E") (pinfunction "EMITTER_E") (pintype "passive"))
      (node (ref "R30") (pin "2") (pinfunction "2_2") (pintype "passive"))
      (node (ref "R30") (pin "21") (pinfunction "2_21") (pintype "passive"))
      (node (ref "U1") (pin "11") (pinfunction "PD7(AIN1)_11") (pintype "bidirectional"))
    )
    (net (code "55") (name "T15") (class "Default")
      (node (ref "OS15") (pin "E") (pinfunction "EMITTER_E") (pintype "passive"))
      (node (ref "R31") (pin "2") (pinfunction "2_2") (pintype "passive"))
      (node (ref "R31") (pin "21") (pinfunction "2_21") (pintype "passive"))
      (node (ref "U1") (pin "12") (pinfunction "PB0(ICP)_12") (pintype "bidirectional"))
    )
    (net (code "56") (name "T16") (class "Default")
      (node (ref "OS16") (pin "E") (pinfunction "EMITTER_E") (pintype "passive"))
      (node (ref "R32") (pin "2") (pinfunction "2_2") (pintype "passive"))
      (node (ref "R32") (pin "21") (pinfunction "2_21") (pintype "passive"))
      (node (ref "U1") (pin "13") (pinfunction "PB1(OC1A)_13") (pintype "bidirectional"))
    )
    (net (code "57") (name "VCC") (class "Default")
      (node (ref "APA1") (pin "VCC") (pinfunction "VCC_VCC") (pintype "power_in"))
      (node (ref "APA10") (pin "VCC") (pinfunction "VCC_VCC") (pintype "power_in"))
      (node (ref "APA11") (pin "VCC") (pinfunction "VCC_VCC") (pintype "power_in"))
      (node (ref "APA12") (pin "VCC") (pinfunction "VCC_VCC") (pintype "power_in"))
      (node (ref "APA13") (pin "VCC") (pinfunction "VCC_VCC") (pintype "power_in"))
      (node (ref "APA14") (pin "VCC") (pinfunction "VCC_VCC") (pintype "power_in"))
      (node (ref "APA15") (pin "VCC") (pinfunction "VCC_VCC") (pintype "power_in"))
      (node (ref "APA16") (pin "VCC") (pinfunction "VCC_VCC") (pintype "power_in"))
      (node (ref "APA2") (pin "VCC") (pinfunction "VCC_VCC") (pintype "power_in"))
      (node (ref "APA3") (pin "VCC") (pinfunction "VCC_VCC") (pintype "power_in"))
      (node (ref "APA4") (pin "VCC") (pinfunction "VCC_VCC") (pintype "power_in"))
      (node (ref "APA5") (pin "VCC") (pinfunction "VCC_VCC") (pintype "power_in"))
      (node (ref "APA6") (pin "VCC") (pinfunction "VCC_VCC") (pintype "power_in"))
      (node (ref "APA7") (pin "VCC") (pinfunction "VCC_VCC") (pintype "power_in"))
      (node (ref "APA8") (pin "VCC") (pinfunction "VCC_VCC") (pintype "power_in"))
      (node (ref "APA9") (pin "VCC") (pinfunction "VCC_VCC") (pintype "power_in"))
      (node (ref "C1") (pin "1") (pinfunction "1_1") (pintype "passive"))
      (node (ref "C10") (pin "1") (pinfunction "1_1") (pintype "passive"))
      (node (ref "C11") (pin "1") (pinfunction "1_1") (pintype "passive"))
      (node (ref "C12") (pin "1") (pinfunction "1_1") (pintype "passive"))
      (node (ref "C13") (pin "1") (pinfunction "1_1") (pintype "passive"))
      (node (ref "C14") (pin "1") (pinfunction "1_1") (pintype "passive"))
      (node (ref "C15") (pin "1") (pinfunction "1_1") (pintype "passive"))
      (node (ref "C16") (pin "1") (pinfunction "1_1") (pintype "passive"))
      (node (ref "C17") (pin "1") (pinfunction "1_1") (pintype "passive"))
      (node (ref "C2") (pin "1") (pinfunction "1_1") (pintype "passive"))
      (node (ref "C3") (pin "1") (pinfunction "1_1") (pintype "passive"))
      (node (ref "C4") (pin "1") (pinfunction "1_1") (pintype "passive"))
      (node (ref "C5") (pin "1") (pinfunction "1_1") (pintype "passive"))
      (node (ref "C6") (pin "1") (pinfunction "1_1") (pintype "passive"))
      (node (ref "C7") (pin "1") (pinfunction "1_1") (pintype "passive"))
      (node (ref "C8") (pin "1") (pinfunction "1_1") (pintype "passive"))
      (node (ref "C9") (pin "1") (pinfunction "1_1") (pintype "passive"))
      (node (ref "JP1") (pin "2") (pinfunction "2_2") (pintype "passive"))
      (node (ref "JP3") (pin "1") (pinfunction "1_1") (pintype "passive"))
      (node (ref "JP3") (pin "2") (pinfunction "2_2") (pintype "passive"))
      (node (ref "JP3") (pin "3") (pinfunction "3_3") (pintype "passive"))
      (node (ref "JP3") (pin "4") (pinfunction "4_4") (pintype "passive"))
      (node (ref "JP3") (pin "5") (pinfunction "5_5") (pintype "passive"))
      (node (ref "JP3") (pin "6") (pinfunction "6_6") (pintype "passive"))
      (node (ref "OS1") (pin "C") (pinfunction "COLLECTOR_C") (pintype "passive"))
      (node (ref "OS10") (pin "C") (pinfunction "COLLECTOR_C") (pintype "passive"))
      (node (ref "OS11") (pin "C") (pinfunction "COLLECTOR_C") (pintype "passive"))
      (node (ref "OS12") (pin "C") (pinfunction "COLLECTOR_C") (pintype "passive"))
      (node (ref "OS13") (pin "C") (pinfunction "COLLECTOR_C") (pintype "passive"))
      (node (ref "OS14") (pin "C") (pinfunction "COLLECTOR_C") (pintype "passive"))
      (node (ref "OS15") (pin "C") (pinfunction "COLLECTOR_C") (pintype "passive"))
      (node (ref "OS16") (pin "C") (pinfunction "COLLECTOR_C") (pintype "passive"))
      (node (ref "OS2") (pin "C") (pinfunction "COLLECTOR_C") (pintype "passive"))
      (node (ref "OS3") (pin "C") (pinfunction "COLLECTOR_C") (pintype "passive"))
      (node (ref "OS4") (pin "C") (pinfunction "COLLECTOR_C") (pintype "passive"))
      (node (ref "OS5") (pin "C") (pinfunction "COLLECTOR_C") (pintype "passive"))
      (node (ref "OS6") (pin "C") (pinfunction "COLLECTOR_C") (pintype "passive"))
      (node (ref "OS7") (pin "C") (pinfunction "COLLECTOR_C") (pintype "passive"))
      (node (ref "OS8") (pin "C") (pinfunction "COLLECTOR_C") (pintype "passive"))
      (node (ref "OS9") (pin "C") (pinfunction "COLLECTOR_C") (pintype "passive"))
      (node (ref "R1") (pin "2") (pinfunction "2_2") (pintype "passive"))
      (node (ref "R1") (pin "21") (pinfunction "2_21") (pintype "passive"))
      (node (ref "R10") (pin "2") (pinfunction "2_2") (pintype "passive"))
      (node (ref "R10") (pin "21") (pinfunction "2_21") (pintype "passive"))
      (node (ref "R11") (pin "2") (pinfunction "2_2") (pintype "passive"))
      (node (ref "R11") (pin "21") (pinfunction "2_21") (pintype "passive"))
      (node (ref "R12") (pin "2") (pinfunction "2_2") (pintype "passive"))
      (node (ref "R12") (pin "21") (pinfunction "2_21") (pintype "passive"))
      (node (ref "R13") (pin "2") (pinfunction "2_2") (pintype "passive"))
      (node (ref "R13") (pin "21") (pinfunction "2_21") (pintype "passive"))
      (node (ref "R14") (pin "2") (pinfunction "2_2") (pintype "passive"))
      (node (ref "R14") (pin "21") (pinfunction "2_21") (pintype "passive"))
      (node (ref "R15") (pin "2") (pinfunction "2_2") (pintype "passive"))
      (node (ref "R15") (pin "21") (pinfunction "2_21") (pintype "passive"))
      (node (ref "R16") (pin "2") (pinfunction "2_2") (pintype "passive"))
      (node (ref "R16") (pin "21") (pinfunction "2_21") (pintype "passive"))
      (node (ref "R2") (pin "2") (pinfunction "2_2") (pintype "passive"))
      (node (ref "R2") (pin "21") (pinfunction "2_21") (pintype "passive"))
      (node (ref "R3") (pin "2") (pinfunction "2_2") (pintype "passive"))
      (node (ref "R3") (pin "21") (pinfunction "2_21") (pintype "passive"))
      (node (ref "R33") (pin "2") (pinfunction "2_2") (pintype "passive"))
      (node (ref "R33") (pin "21") (pinfunction "2_21") (pintype "passive"))
      (node (ref "R4") (pin "2") (pinfunction "2_2") (pintype "passive"))
      (node (ref "R4") (pin "21") (pinfunction "2_21") (pintype "passive"))
      (node (ref "R5") (pin "2") (pinfunction "2_2") (pintype "passive"))
      (node (ref "R5") (pin "21") (pinfunction "2_21") (pintype "passive"))
      (node (ref "R6") (pin "2") (pinfunction "2_2") (pintype "passive"))
      (node (ref "R6") (pin "21") (pinfunction "2_21") (pintype "passive"))
      (node (ref "R7") (pin "2") (pinfunction "2_2") (pintype "passive"))
      (node (ref "R7") (pin "21") (pinfunction "2_21") (pintype "passive"))
      (node (ref "R8") (pin "2") (pinfunction "2_2") (pintype "passive"))
      (node (ref "R8") (pin "21") (pinfunction "2_21") (pintype "passive"))
      (node (ref "R9") (pin "2") (pinfunction "2_2") (pintype "passive"))
      (node (ref "R9") (pin "21") (pinfunction "2_21") (pintype "passive"))
      (node (ref "U1") (pin "18") (pinfunction "AVCC_18") (pintype "bidirectional"))
      (node (ref "U1") (pin "20") (pinfunction "AREF_20") (pintype "bidirectional"))
      (node (ref "U1") (pin "4") (pinfunction "VCC_4") (pintype "bidirectional"))
      (node (ref "U1") (pin "6") (pinfunction "VCC_6") (pintype "bidirectional"))
      (node (ref "X1") (pin "1") (pinfunction "1_1") (pintype "passive"))
    )
    (net (code "58") (name "unconnected-(U1-PB2(SS{slash}OC1B)-Pad14)") (class "Default")
      (node (ref "U1") (pin "14") (pinfunction "PB2(SS/OC1B)_14") (pintype "bidirectional"))
    )
    (net (code "59") (name "unconnected-(U1-PB6(XTAL1{slash}TOSC1)-Pad7)") (class "Default")
      (node (ref "U1") (pin "7") (pinfunction "PB6(XTAL1/TOSC1)_7") (pintype "bidirectional"))
    )
    (net (code "60") (name "unconnected-(U1-PB7(XTAL2{slash}TOSC2)-Pad8)") (class "Default")
      (node (ref "U1") (pin "8") (pinfunction "PB7(XTAL2/TOSC2)_8") (pintype "bidirectional"))
    )
  )
)
